# HIVE_BOARD_MCU.net
KiCad netlist of a schematic drawn in Altium Designer
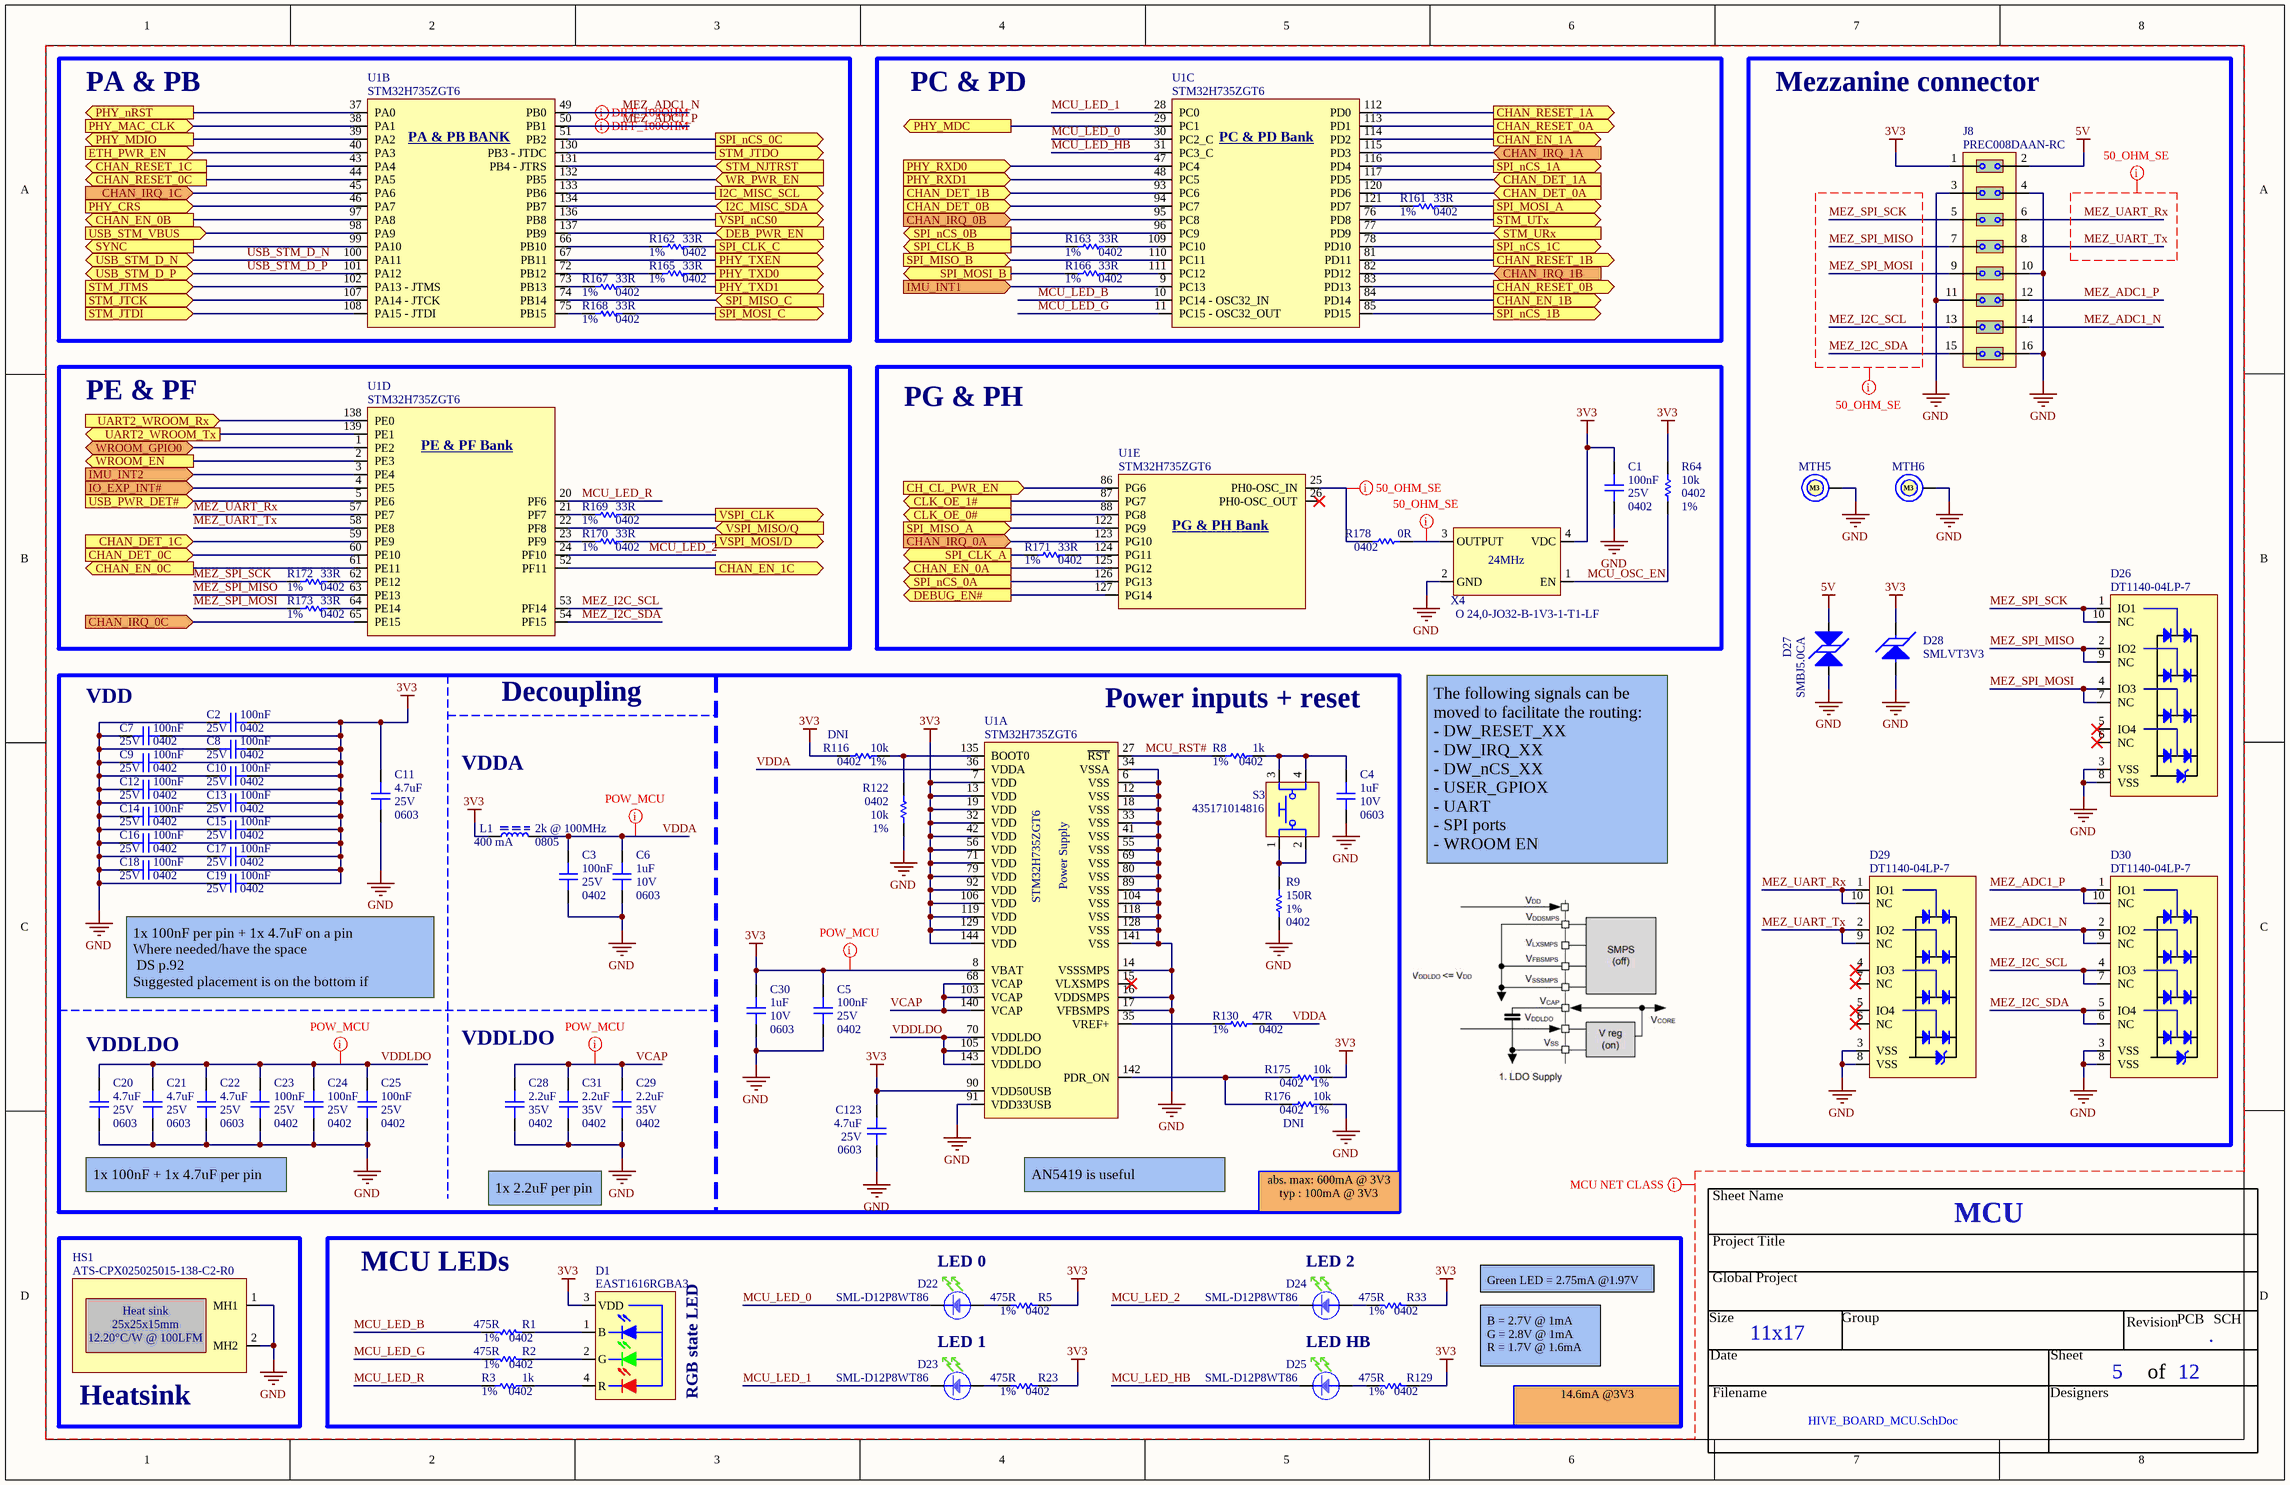
[diagram p0: HIVE_BOARD_MCU.SchDoc]

(export (version "E")
  (design (tool "Eeschema 10.0.6"))
  (components
    (comp (ref "C1")
      (value "100nF")
      (footprint "CAP_CER_0402")
      (description "CAP - CER 0.1µF 10% 25V X7R - 0402")
      (fields
        (field (name "TOLERANCE") "10%")
        (field (name "PACKAGE") "0402")
        (field (name "VOLTAGE RATING") "25V")
        (field (name "Comment") "CGA2B3X7R1E104K050BB")
        (field (name "CREATEDBY/DATE") "Nicolas Roy 2018-11-07")
        (field (name "VERIFIEDBY") "Nicolas V. (2019-01-22)")
      )
      (libsource (lib "GRAMS_MASTER_LIB") (part "CAP_CER_CGA2B3X7R1E104K050BB"))
    )
    (comp (ref "C2")
      (value "100nF")
      (footprint "CAP_CER_0402")
      (description "CAP - CER 0.1µF 10% 25V X7R - 0402")
      (fields
        (field (name "TOLERANCE") "10%")
        (field (name "PACKAGE") "0402")
        (field (name "VOLTAGE RATING") "25V")
        (field (name "Comment") "CGA2B3X7R1E104K050BB")
        (field (name "CREATEDBY/DATE") "Nicolas Roy 2018-11-07")
        (field (name "VERIFIEDBY") "Nicolas V. (2019-01-22)")
      )
      (libsource (lib "GRAMS_MASTER_LIB") (part "CAP_CER_CGA2B3X7R1E104K050BB"))
    )
    (comp (ref "C3")
      (value "100nF")
      (footprint "CAP_CER_0402")
      (description "CAP - CER 0.1µF 10% 25V X7R - 0402")
      (fields
        (field (name "TOLERANCE") "10%")
        (field (name "PACKAGE") "0402")
        (field (name "VOLTAGE RATING") "25V")
        (field (name "Comment") "CGA2B3X7R1E104K050BB")
        (field (name "CREATEDBY/DATE") "Nicolas Roy 2018-11-07")
        (field (name "VERIFIEDBY") "Nicolas V. (2019-01-22)")
      )
      (libsource (lib "GRAMS_MASTER_LIB") (part "CAP_CER_CGA2B3X7R1E104K050BB"))
    )
    (comp (ref "C4")
      (value "1uF")
      (footprint "CAP_CER_0603")
      (description "CAP - CER 1uF 10V 10% X5R - 0603")
      (fields
        (field (name "TOLERANCE") "10%")
        (field (name "PACKAGE") "0603")
        (field (name "VOLTAGE RATING") "10V")
        (field (name "Comment") "C0603C105K8PACTU")
        (field (name "CREATEDBY/DATE") "Hubert Dube - 21/07/20")
        (field (name "VERIFIEDBY") "Louis-Daniel Gaulin - 21/07/20")
      )
      (libsource (lib "SWARMUS_LIB") (part "CAP_CER_C0603C105K8PACTU"))
    )
    (comp (ref "C5")
      (value "100nF")
      (footprint "CAP_CER_0402")
      (description "CAP - CER 0.1µF 10% 25V X7R - 0402")
      (fields
        (field (name "TOLERANCE") "10%")
        (field (name "PACKAGE") "0402")
        (field (name "VOLTAGE RATING") "25V")
        (field (name "Comment") "CGA2B3X7R1E104K050BB")
        (field (name "CREATEDBY/DATE") "Nicolas Roy 2018-11-07")
        (field (name "VERIFIEDBY") "Nicolas V. (2019-01-22)")
      )
      (libsource (lib "GRAMS_MASTER_LIB") (part "CAP_CER_CGA2B3X7R1E104K050BB"))
    )
    (comp (ref "C6")
      (value "1uF")
      (footprint "CAP_CER_0603")
      (description "CAP - CER 1uF 10V 10% X5R - 0603")
      (fields
        (field (name "TOLERANCE") "10%")
        (field (name "PACKAGE") "0603")
        (field (name "VOLTAGE RATING") "10V")
        (field (name "Comment") "C0603C105K8PACTU")
        (field (name "CREATEDBY/DATE") "Hubert Dube - 21/07/20")
        (field (name "VERIFIEDBY") "Louis-Daniel Gaulin - 21/07/20")
      )
      (libsource (lib "SWARMUS_LIB") (part "CAP_CER_C0603C105K8PACTU"))
    )
    (comp (ref "C7")
      (value "100nF")
      (footprint "CAP_CER_0402")
      (description "CAP - CER 0.1µF 10% 25V X7R - 0402")
      (fields
        (field (name "TOLERANCE") "10%")
        (field (name "PACKAGE") "0402")
        (field (name "VOLTAGE RATING") "25V")
        (field (name "Comment") "CGA2B3X7R1E104K050BB")
        (field (name "CREATEDBY/DATE") "Nicolas Roy 2018-11-07")
        (field (name "VERIFIEDBY") "Nicolas V. (2019-01-22)")
      )
      (libsource (lib "GRAMS_MASTER_LIB") (part "CAP_CER_CGA2B3X7R1E104K050BB"))
    )
    (comp (ref "C8")
      (value "100nF")
      (footprint "CAP_CER_0402")
      (description "CAP - CER 0.1µF 10% 25V X7R - 0402")
      (fields
        (field (name "TOLERANCE") "10%")
        (field (name "PACKAGE") "0402")
        (field (name "VOLTAGE RATING") "25V")
        (field (name "Comment") "CGA2B3X7R1E104K050BB")
        (field (name "CREATEDBY/DATE") "Nicolas Roy 2018-11-07")
        (field (name "VERIFIEDBY") "Nicolas V. (2019-01-22)")
      )
      (libsource (lib "GRAMS_MASTER_LIB") (part "CAP_CER_CGA2B3X7R1E104K050BB"))
    )
    (comp (ref "C9")
      (value "100nF")
      (footprint "CAP_CER_0402")
      (description "CAP - CER 0.1µF 10% 25V X7R - 0402")
      (fields
        (field (name "TOLERANCE") "10%")
        (field (name "PACKAGE") "0402")
        (field (name "VOLTAGE RATING") "25V")
        (field (name "Comment") "CGA2B3X7R1E104K050BB")
        (field (name "CREATEDBY/DATE") "Nicolas Roy 2018-11-07")
        (field (name "VERIFIEDBY") "Nicolas V. (2019-01-22)")
      )
      (libsource (lib "GRAMS_MASTER_LIB") (part "CAP_CER_CGA2B3X7R1E104K050BB"))
    )
    (comp (ref "C10")
      (value "100nF")
      (footprint "CAP_CER_0402")
      (description "CAP - CER 0.1µF 10% 25V X7R - 0402")
      (fields
        (field (name "TOLERANCE") "10%")
        (field (name "PACKAGE") "0402")
        (field (name "VOLTAGE RATING") "25V")
        (field (name "Comment") "CGA2B3X7R1E104K050BB")
        (field (name "CREATEDBY/DATE") "Nicolas Roy 2018-11-07")
        (field (name "VERIFIEDBY") "Nicolas V. (2019-01-22)")
      )
      (libsource (lib "GRAMS_MASTER_LIB") (part "CAP_CER_CGA2B3X7R1E104K050BB"))
    )
    (comp (ref "C11")
      (value "4.7uF")
      (footprint "CAP_CER_0603")
      (description "CAP - CER 4.7µF 20% 25V X5R - 0603")
      (fields
        (field (name "TOLERANCE") "20%")
        (field (name "PACKAGE") "0603")
        (field (name "VOLTAGE RATING") "25V")
        (field (name "Comment") "CL10A475MA8NQNC")
        (field (name "CREATEDBY/DATE") "Nicolas Roy 2018-11-21")
        (field (name "VERIFIEDBY") "Nicolas V. (2019-01-22)")
      )
      (libsource (lib "GRAMS_MASTER_LIB") (part "CAP_CER_CL10A475MA8NQNC"))
    )
    (comp (ref "C12")
      (value "100nF")
      (footprint "CAP_CER_0402")
      (description "CAP - CER 0.1µF 10% 25V X7R - 0402")
      (fields
        (field (name "TOLERANCE") "10%")
        (field (name "PACKAGE") "0402")
        (field (name "VOLTAGE RATING") "25V")
        (field (name "Comment") "CGA2B3X7R1E104K050BB")
        (field (name "CREATEDBY/DATE") "Nicolas Roy 2018-11-07")
        (field (name "VERIFIEDBY") "Nicolas V. (2019-01-22)")
      )
      (libsource (lib "GRAMS_MASTER_LIB") (part "CAP_CER_CGA2B3X7R1E104K050BB"))
    )
    (comp (ref "C13")
      (value "100nF")
      (footprint "CAP_CER_0402")
      (description "CAP - CER 0.1µF 10% 25V X7R - 0402")
      (fields
        (field (name "TOLERANCE") "10%")
        (field (name "PACKAGE") "0402")
        (field (name "VOLTAGE RATING") "25V")
        (field (name "Comment") "CGA2B3X7R1E104K050BB")
        (field (name "CREATEDBY/DATE") "Nicolas Roy 2018-11-07")
        (field (name "VERIFIEDBY") "Nicolas V. (2019-01-22)")
      )
      (libsource (lib "GRAMS_MASTER_LIB") (part "CAP_CER_CGA2B3X7R1E104K050BB"))
    )
    (comp (ref "C14")
      (value "100nF")
      (footprint "CAP_CER_0402")
      (description "CAP - CER 0.1µF 10% 25V X7R - 0402")
      (fields
        (field (name "TOLERANCE") "10%")
        (field (name "PACKAGE") "0402")
        (field (name "VOLTAGE RATING") "25V")
        (field (name "Comment") "CGA2B3X7R1E104K050BB")
        (field (name "CREATEDBY/DATE") "Nicolas Roy 2018-11-07")
        (field (name "VERIFIEDBY") "Nicolas V. (2019-01-22)")
      )
      (libsource (lib "GRAMS_MASTER_LIB") (part "CAP_CER_CGA2B3X7R1E104K050BB"))
    )
    (comp (ref "C15")
      (value "100nF")
      (footprint "CAP_CER_0402")
      (description "CAP - CER 0.1µF 10% 25V X7R - 0402")
      (fields
        (field (name "TOLERANCE") "10%")
        (field (name "PACKAGE") "0402")
        (field (name "VOLTAGE RATING") "25V")
        (field (name "Comment") "CGA2B3X7R1E104K050BB")
        (field (name "CREATEDBY/DATE") "Nicolas Roy 2018-11-07")
        (field (name "VERIFIEDBY") "Nicolas V. (2019-01-22)")
      )
      (libsource (lib "GRAMS_MASTER_LIB") (part "CAP_CER_CGA2B3X7R1E104K050BB"))
    )
    (comp (ref "C16")
      (value "100nF")
      (footprint "CAP_CER_0402")
      (description "CAP - CER 0.1µF 10% 25V X7R - 0402")
      (fields
        (field (name "TOLERANCE") "10%")
        (field (name "PACKAGE") "0402")
        (field (name "VOLTAGE RATING") "25V")
        (field (name "Comment") "CGA2B3X7R1E104K050BB")
        (field (name "CREATEDBY/DATE") "Nicolas Roy 2018-11-07")
        (field (name "VERIFIEDBY") "Nicolas V. (2019-01-22)")
      )
      (libsource (lib "GRAMS_MASTER_LIB") (part "CAP_CER_CGA2B3X7R1E104K050BB"))
    )
    (comp (ref "C17")
      (value "100nF")
      (footprint "CAP_CER_0402")
      (description "CAP - CER 0.1µF 10% 25V X7R - 0402")
      (fields
        (field (name "TOLERANCE") "10%")
        (field (name "PACKAGE") "0402")
        (field (name "VOLTAGE RATING") "25V")
        (field (name "Comment") "CGA2B3X7R1E104K050BB")
        (field (name "CREATEDBY/DATE") "Nicolas Roy 2018-11-07")
        (field (name "VERIFIEDBY") "Nicolas V. (2019-01-22)")
      )
      (libsource (lib "GRAMS_MASTER_LIB") (part "CAP_CER_CGA2B3X7R1E104K050BB"))
    )
    (comp (ref "C18")
      (value "100nF")
      (footprint "CAP_CER_0402")
      (description "CAP - CER 0.1µF 10% 25V X7R - 0402")
      (fields
        (field (name "TOLERANCE") "10%")
        (field (name "PACKAGE") "0402")
        (field (name "VOLTAGE RATING") "25V")
        (field (name "Comment") "CGA2B3X7R1E104K050BB")
        (field (name "CREATEDBY/DATE") "Nicolas Roy 2018-11-07")
        (field (name "VERIFIEDBY") "Nicolas V. (2019-01-22)")
      )
      (libsource (lib "GRAMS_MASTER_LIB") (part "CAP_CER_CGA2B3X7R1E104K050BB"))
    )
    (comp (ref "C19")
      (value "100nF")
      (footprint "CAP_CER_0402")
      (description "CAP - CER 0.1µF 10% 25V X7R - 0402")
      (fields
        (field (name "TOLERANCE") "10%")
        (field (name "PACKAGE") "0402")
        (field (name "VOLTAGE RATING") "25V")
        (field (name "Comment") "CGA2B3X7R1E104K050BB")
        (field (name "CREATEDBY/DATE") "Nicolas Roy 2018-11-07")
        (field (name "VERIFIEDBY") "Nicolas V. (2019-01-22)")
      )
      (libsource (lib "GRAMS_MASTER_LIB") (part "CAP_CER_CGA2B3X7R1E104K050BB"))
    )
    (comp (ref "C20")
      (value "4.7uF")
      (footprint "CAP_CER_0603")
      (description "CAP - CER 4.7µF 20% 25V X5R - 0603")
      (fields
        (field (name "TOLERANCE") "20%")
        (field (name "PACKAGE") "0603")
        (field (name "VOLTAGE RATING") "25V")
        (field (name "Comment") "CL10A475MA8NQNC")
        (field (name "CREATEDBY/DATE") "Nicolas Roy 2018-11-21")
        (field (name "VERIFIEDBY") "Nicolas V. (2019-01-22)")
      )
      (libsource (lib "GRAMS_MASTER_LIB") (part "CAP_CER_CL10A475MA8NQNC"))
    )
    (comp (ref "C21")
      (value "4.7uF")
      (footprint "CAP_CER_0603")
      (description "CAP - CER 4.7µF 20% 25V X5R - 0603")
      (fields
        (field (name "TOLERANCE") "20%")
        (field (name "PACKAGE") "0603")
        (field (name "VOLTAGE RATING") "25V")
        (field (name "Comment") "CL10A475MA8NQNC")
        (field (name "CREATEDBY/DATE") "Nicolas Roy 2018-11-21")
        (field (name "VERIFIEDBY") "Nicolas V. (2019-01-22)")
      )
      (libsource (lib "GRAMS_MASTER_LIB") (part "CAP_CER_CL10A475MA8NQNC"))
    )
    (comp (ref "C22")
      (value "4.7uF")
      (footprint "CAP_CER_0603")
      (description "CAP - CER 4.7µF 20% 25V X5R - 0603")
      (fields
        (field (name "TOLERANCE") "20%")
        (field (name "PACKAGE") "0603")
        (field (name "VOLTAGE RATING") "25V")
        (field (name "Comment") "CL10A475MA8NQNC")
        (field (name "CREATEDBY/DATE") "Nicolas Roy 2018-11-21")
        (field (name "VERIFIEDBY") "Nicolas V. (2019-01-22)")
      )
      (libsource (lib "GRAMS_MASTER_LIB") (part "CAP_CER_CL10A475MA8NQNC"))
    )
    (comp (ref "C23")
      (value "100nF")
      (footprint "CAP_CER_0402")
      (description "CAP - CER 0.1µF 10% 25V X7R - 0402")
      (fields
        (field (name "TOLERANCE") "10%")
        (field (name "PACKAGE") "0402")
        (field (name "VOLTAGE RATING") "25V")
        (field (name "Comment") "CGA2B3X7R1E104K050BB")
        (field (name "CREATEDBY/DATE") "Nicolas Roy 2018-11-07")
        (field (name "VERIFIEDBY") "Nicolas V. (2019-01-22)")
      )
      (libsource (lib "GRAMS_MASTER_LIB") (part "CAP_CER_CGA2B3X7R1E104K050BB"))
    )
    (comp (ref "C24")
      (value "100nF")
      (footprint "CAP_CER_0402")
      (description "CAP - CER 0.1µF 10% 25V X7R - 0402")
      (fields
        (field (name "TOLERANCE") "10%")
        (field (name "PACKAGE") "0402")
        (field (name "VOLTAGE RATING") "25V")
        (field (name "Comment") "CGA2B3X7R1E104K050BB")
        (field (name "CREATEDBY/DATE") "Nicolas Roy 2018-11-07")
        (field (name "VERIFIEDBY") "Nicolas V. (2019-01-22)")
      )
      (libsource (lib "GRAMS_MASTER_LIB") (part "CAP_CER_CGA2B3X7R1E104K050BB"))
    )
    (comp (ref "C25")
      (value "100nF")
      (footprint "CAP_CER_0402")
      (description "CAP - CER 0.1µF 10% 25V X7R - 0402")
      (fields
        (field (name "TOLERANCE") "10%")
        (field (name "PACKAGE") "0402")
        (field (name "VOLTAGE RATING") "25V")
        (field (name "Comment") "CGA2B3X7R1E104K050BB")
        (field (name "CREATEDBY/DATE") "Nicolas Roy 2018-11-07")
        (field (name "VERIFIEDBY") "Nicolas V. (2019-01-22)")
      )
      (libsource (lib "GRAMS_MASTER_LIB") (part "CAP_CER_CGA2B3X7R1E104K050BB"))
    )
    (comp (ref "C28")
      (value "2.2uF")
      (footprint "CAP_CER_0402")
      (description "CAP - CER 2.2µF 10% 35V X5R - 0402")
      (fields
        (field (name "TOLERANCE") "10%")
        (field (name "PACKAGE") "0402")
        (field (name "VOLTAGE RATING") "35V")
        (field (name "Comment") "C1005X5R1V225K050BC")
        (field (name "CREATEDBY/DATE") "Nicolas Roy 2018-10-17")
        (field (name "VERIFIEDBY") "Caroline Paulin - 18 janv 2018")
      )
      (libsource (lib "GRAMS_MASTER_LIB") (part "CAP_CER_C1005X5R1V225K050BC"))
    )
    (comp (ref "C29")
      (value "2.2uF")
      (footprint "CAP_CER_0402")
      (description "CAP - CER 2.2µF 10% 35V X5R - 0402")
      (fields
        (field (name "TOLERANCE") "10%")
        (field (name "PACKAGE") "0402")
        (field (name "VOLTAGE RATING") "35V")
        (field (name "Comment") "C1005X5R1V225K050BC")
        (field (name "CREATEDBY/DATE") "Nicolas Roy 2018-10-17")
        (field (name "VERIFIEDBY") "Caroline Paulin - 18 janv 2018")
      )
      (libsource (lib "GRAMS_MASTER_LIB") (part "CAP_CER_C1005X5R1V225K050BC"))
    )
    (comp (ref "C30")
      (value "1uF")
      (footprint "CAP_CER_0603")
      (description "CAP - CER 1uF 10V 10% X5R - 0603")
      (fields
        (field (name "TOLERANCE") "10%")
        (field (name "PACKAGE") "0603")
        (field (name "VOLTAGE RATING") "10V")
        (field (name "Comment") "C0603C105K8PACTU")
        (field (name "CREATEDBY/DATE") "Hubert Dube - 21/07/20")
        (field (name "VERIFIEDBY") "Louis-Daniel Gaulin - 21/07/20")
      )
      (libsource (lib "SWARMUS_LIB") (part "CAP_CER_C0603C105K8PACTU"))
    )
    (comp (ref "C31")
      (value "2.2uF")
      (footprint "CAP_CER_0402")
      (description "CAP - CER 2.2µF 10% 35V X5R - 0402")
      (fields
        (field (name "TOLERANCE") "10%")
        (field (name "PACKAGE") "0402")
        (field (name "VOLTAGE RATING") "35V")
        (field (name "Comment") "C1005X5R1V225K050BC")
        (field (name "CREATEDBY/DATE") "Nicolas Roy 2018-10-17")
        (field (name "VERIFIEDBY") "Caroline Paulin - 18 janv 2018")
      )
      (libsource (lib "GRAMS_MASTER_LIB") (part "CAP_CER_C1005X5R1V225K050BC"))
    )
    (comp (ref "C123")
      (value "4.7uF")
      (footprint "CAP_CER_0603")
      (description "CAP - CER 4.7µF 20% 25V X5R - 0603")
      (fields
        (field (name "TOLERANCE") "20%")
        (field (name "PACKAGE") "0603")
        (field (name "VOLTAGE RATING") "25V")
        (field (name "Comment") "CL10A475MA8NQNC")
        (field (name "CREATEDBY/DATE") "Nicolas Roy 2018-11-21")
        (field (name "VERIFIEDBY") "Nicolas V. (2019-01-22)")
      )
      (libsource (lib "GRAMS_MASTER_LIB") (part "CAP_CER_CL10A475MA8NQNC"))
    )
    (comp (ref "D1")
      (value "EAST1616RGBA3")
      (footprint "DIO_EAST1616RGBA3")
      (fields
        (field (name "TOLERANCE") "±50ppm")
        (field (name "CREATEDBY/DATE") "Hubert Dube - 26/02/2021")
        (field (name "VERIFIEDBY") "PA + Hubert Dube - 19/03/2021")
      )
      (libsource (lib "SWARMUS_LIB") (part "DIO_EAST1616RGBA3"))
    )
    (comp (ref "D22")
      (value "SML-D12P8WT86")
      (footprint "LED_SML-D12P8WT86")
      (description "LED - GREEN DIFFUSED 0603 SMD - 0603")
      (fields
        (field (name "CREATEDBY/DATE") "Keven Deslandes - 2018/11/21")
        (field (name "VERIFIEDBY") "Caroline Paulin - 13 février 2019")
      )
      (libsource (lib "GRAMS_MASTER_LIB") (part "LED_SML-D12P8WT86"))
    )
    (comp (ref "D23")
      (value "SML-D12P8WT86")
      (footprint "LED_SML-D12P8WT86")
      (description "LED - GREEN DIFFUSED 0603 SMD - 0603")
      (fields
        (field (name "CREATEDBY/DATE") "Keven Deslandes - 2018/11/21")
        (field (name "VERIFIEDBY") "Caroline Paulin - 13 février 2019")
      )
      (libsource (lib "GRAMS_MASTER_LIB") (part "LED_SML-D12P8WT86"))
    )
    (comp (ref "D24")
      (value "SML-D12P8WT86")
      (footprint "LED_SML-D12P8WT86")
      (description "LED - GREEN DIFFUSED 0603 SMD - 0603")
      (fields
        (field (name "CREATEDBY/DATE") "Keven Deslandes - 2018/11/21")
        (field (name "VERIFIEDBY") "Caroline Paulin - 13 février 2019")
      )
      (libsource (lib "GRAMS_MASTER_LIB") (part "LED_SML-D12P8WT86"))
    )
    (comp (ref "D25")
      (value "SML-D12P8WT86")
      (footprint "LED_SML-D12P8WT86")
      (description "LED - GREEN DIFFUSED 0603 SMD - 0603")
      (fields
        (field (name "CREATEDBY/DATE") "Keven Deslandes - 2018/11/21")
        (field (name "VERIFIEDBY") "Caroline Paulin - 13 février 2019")
      )
      (libsource (lib "GRAMS_MASTER_LIB") (part "LED_SML-D12P8WT86"))
    )
    (comp (ref "D26")
      (value "DT1140-04LP-7")
      (footprint "TVS_DATA_DT1140-04LP-7")
      (description "TVS - DIODE 5.5V 10V - 10-UFDFN")
      (fields
        (field (name "CREATEDBY/DATE") "Joël Lemay 2019-11-20")
        (field (name "VERIFIEDBY") "C.Paulin - 21/11/2019")
      )
      (libsource (lib "GRAMS_MASTER_LIB") (part "TVS_DATA_DT1140-04LP-7"))
    )
    (comp (ref "D27")
      (value "SMBJ5.0CA")
      (footprint "TVS_PWR_SMBJ5.0CA")
      (description "TVS - BIDIR 5V 9.2V 600W - DO214AA")
      (fields
        (field (name "CREATEDBY/DATE") "Jonathan Bouchard - 2019-03-22")
        (field (name "VERIFIEDBY") "Nicolas V. (2019-05-06)")
      )
      (libsource (lib "GRAMS_MASTER_LIB") (part "TVS_PWR_SMBJ5.0CA"))
    )
    (comp (ref "D28")
      (value "SMLVT3V3")
      (footprint "TVS_POW_SMLVT3V3")
      (description "TVS - 3.3V 10.3V 600W - DO214AA")
      (fields
        (field (name "CREATEDBY/DATE") "Jonathan Bouchard - 2019-04-27")
        (field (name "VERIFIEDBY") "Nicolas V. (2019-05-06)")
      )
      (libsource (lib "GRAMS_MASTER_LIB") (part "TVS_POW_SMLVT3V3"))
    )
    (comp (ref "D29")
      (value "DT1140-04LP-7")
      (footprint "TVS_DATA_DT1140-04LP-7")
      (description "TVS - DIODE 5.5V 10V - 10-UFDFN")
      (fields
        (field (name "CREATEDBY/DATE") "Joël Lemay 2019-11-20")
        (field (name "VERIFIEDBY") "C.Paulin - 21/11/2019")
      )
      (libsource (lib "GRAMS_MASTER_LIB") (part "TVS_DATA_DT1140-04LP-7"))
    )
    (comp (ref "D30")
      (value "DT1140-04LP-7")
      (footprint "TVS_DATA_DT1140-04LP-7")
      (description "TVS - DIODE 5.5V 10V - 10-UFDFN")
      (fields
        (field (name "CREATEDBY/DATE") "Joël Lemay 2019-11-20")
        (field (name "VERIFIEDBY") "C.Paulin - 21/11/2019")
      )
      (libsource (lib "GRAMS_MASTER_LIB") (part "TVS_DATA_DT1140-04LP-7"))
    )
    (comp (ref "HS1")
      (value "ATS-CPX025025015-138-C2-R0")
      (footprint "THE_HS_ATS-CPX025025015-138-C2-R0")
      (description "THE_HS - Heat Sink  25x25x15 mm - TH M3")
      (fields
        (field (name "CREATEDBY/DATE") "Philippe Arsenault/2021-04-08")
        (field (name "VERIFIEDBY") "Louis-Daniel Gaulin / 14-04-2021")
      )
      (libsource (lib "SWARMUS_LIB") (part "THE_HS_ATS-CPX025025015-138-C2-R0"))
    )
    (comp (ref "J8")
      (value "PREC008DAAN-RC")
      (footprint "CON_HDR_PREC008DAAN-RC")
      (description "CON - Connector Header Through Hole 16 position 0.100\" (2.54mm)")
      (fields
        (field (name "VERIFIEDBY") "Philippe Arsenault/2021-03-25")
        (field (name "CREATEDBY/DATE") "Hubert Dube -  16/03/2021")
      )
      (libsource (lib "SWARMUS_LIB") (part "CON_HDR_PREC008DAAN-RC"))
    )
    (comp (ref "L1")
      (value "2k @ 100MHz")
      (footprint "FER_0805")
      (description "FER - FERRITE BEAD 2 KOHM @ 100 MHz 400 mA - 0805")
      (fields
        (field (name "CURRENT RATING") "400 mA")
        (field (name "PACKAGE") "0805")
        (field (name "Comment") "MMZ2012Y202BT000")
        (field (name "CREATEDBY/DATE") "Hubert Dube - 7/02/2021")
        (field (name "VERIFIEDBY") "Philippe Arsenault/ 2021-03-13")
      )
      (libsource (lib "SWARMUS_LIB") (part "FER_MMZ2012Y202BT000"))
    )
    (comp (ref "MTH5")
      (value "M3")
      (footprint "MTH_M3")
      (description "MTH - MOUNTING HOLE M3 PLATED - M3")
      (fields
        (field (name "CREATEDBY/DATE") "Jonathan Bouchard 2018-07-23")
        (field (name "VERIFIEDBY") "Arnaud Samson 23-07-18")
      )
      (libsource (lib "GRAMS_MASTER_LIB") (part "MTH_M3"))
    )
    (comp (ref "MTH6")
      (value "M3")
      (footprint "MTH_M3")
      (description "MTH - MOUNTING HOLE M3 PLATED - M3")
      (fields
        (field (name "CREATEDBY/DATE") "Jonathan Bouchard 2018-07-23")
        (field (name "VERIFIEDBY") "Arnaud Samson 23-07-18")
      )
      (libsource (lib "GRAMS_MASTER_LIB") (part "MTH_M3"))
    )
    (comp (ref "R1")
      (value "475R")
      (footprint "RES_0402")
      (description "RES - 475R 1% 1/10W- 0402")
      (fields
        (field (name "TOLERANCE") "1%")
        (field (name "PACKAGE") "0402")
        (field (name "Comment") "ERJ-2RKF4750X")
        (field (name "CREATEDBY/DATE") "Keven Deslandes 2018-10-17")
        (field (name "VERIFIEDBY") "Carolilne Paulin - 18/12/2018")
      )
      (libsource (lib "GRAMS_MASTER_LIB") (part "RES_ERJ-2RKF4750X"))
    )
    (comp (ref "R2")
      (value "475R")
      (footprint "RES_0402")
      (description "RES - 475R 1% 1/10W- 0402")
      (fields
        (field (name "TOLERANCE") "1%")
        (field (name "PACKAGE") "0402")
        (field (name "Comment") "ERJ-2RKF4750X")
        (field (name "CREATEDBY/DATE") "Keven Deslandes 2018-10-17")
        (field (name "VERIFIEDBY") "Carolilne Paulin - 18/12/2018")
      )
      (libsource (lib "GRAMS_MASTER_LIB") (part "RES_ERJ-2RKF4750X"))
    )
    (comp (ref "R3")
      (value "1k")
      (footprint "RES_0402")
      (description "RES - 1K OHM 1% 1/16W - 0402")
      (fields
        (field (name "TOLERANCE") "1%")
        (field (name "PACKAGE") "0402")
        (field (name "Comment") "RC0402FR-071KL")
        (field (name "CREATEDBY/DATE") "Jonathan Bouchard 2018-07-05")
        (field (name "VERIFIEDBY") "Arnaud Samson 16-07-18")
      )
      (libsource (lib "GRAMS_MASTER_LIB") (part "RES_RC0402FR-071KL"))
    )
    (comp (ref "R5")
      (value "475R")
      (footprint "RES_0402")
      (description "RES - 475R 1% 1/10W- 0402")
      (fields
        (field (name "TOLERANCE") "1%")
        (field (name "PACKAGE") "0402")
        (field (name "Comment") "ERJ-2RKF4750X")
        (field (name "CREATEDBY/DATE") "Keven Deslandes 2018-10-17")
        (field (name "VERIFIEDBY") "Carolilne Paulin - 18/12/2018")
      )
      (libsource (lib "GRAMS_MASTER_LIB") (part "RES_ERJ-2RKF4750X"))
    )
    (comp (ref "R8")
      (value "1k")
      (footprint "RES_0402")
      (description "RES - 1K OHM 1% 1/16W - 0402")
      (fields
        (field (name "TOLERANCE") "1%")
        (field (name "PACKAGE") "0402")
        (field (name "Comment") "RC0402FR-071KL")
        (field (name "CREATEDBY/DATE") "Jonathan Bouchard 2018-07-05")
        (field (name "VERIFIEDBY") "Arnaud Samson 16-07-18")
      )
      (libsource (lib "GRAMS_MASTER_LIB") (part "RES_RC0402FR-071KL"))
    )
    (comp (ref "R9")
      (value "150R")
      (footprint "RES_0402")
      (description "RES - 150R 1% 1/16W - 0402")
      (fields
        (field (name "TOLERANCE") "1%")
        (field (name "PACKAGE") "0402")
        (field (name "Comment") "RC0402FR-07150RL")
        (field (name "CREATEDBY/DATE") "Jonathan Bouchard 2019-03-25")
        (field (name "VERIFIEDBY") "Nicolas V. (2019-05-02)")
      )
      (libsource (lib "GRAMS_MASTER_LIB") (part "RES_RC0402FR-07150RL"))
    )
    (comp (ref "R23")
      (value "475R")
      (footprint "RES_0402")
      (description "RES - 475R 1% 1/10W- 0402")
      (fields
        (field (name "TOLERANCE") "1%")
        (field (name "PACKAGE") "0402")
        (field (name "Comment") "ERJ-2RKF4750X")
        (field (name "CREATEDBY/DATE") "Keven Deslandes 2018-10-17")
        (field (name "VERIFIEDBY") "Carolilne Paulin - 18/12/2018")
      )
      (libsource (lib "GRAMS_MASTER_LIB") (part "RES_ERJ-2RKF4750X"))
    )
    (comp (ref "R33")
      (value "475R")
      (footprint "RES_0402")
      (description "RES - 475R 1% 1/10W- 0402")
      (fields
        (field (name "TOLERANCE") "1%")
        (field (name "PACKAGE") "0402")
        (field (name "Comment") "ERJ-2RKF4750X")
        (field (name "CREATEDBY/DATE") "Keven Deslandes 2018-10-17")
        (field (name "VERIFIEDBY") "Carolilne Paulin - 18/12/2018")
      )
      (libsource (lib "GRAMS_MASTER_LIB") (part "RES_ERJ-2RKF4750X"))
    )
    (comp (ref "R64")
      (value "10k")
      (footprint "RES_0402")
      (description "RES - 10K OHMS 1% 1/16W - 0402")
      (fields
        (field (name "TOLERANCE") "1%")
        (field (name "PACKAGE") "0402")
        (field (name "Comment") "RC0402FR-0710KL")
        (field (name "CREATEDBY/DATE") "Nicolas V. (2018-11-20)")
        (field (name "VERIFIEDBY") "Nicolas V. (2018-11-20)")
      )
      (libsource (lib "GRAMS_MASTER_LIB") (part "RES_RC0402FR-0710KL"))
    )
    (comp (ref "R116")
      (value "10k")
      (footprint "RES_0402")
      (description "RES - 10K OHMS 1% 1/16W - 0402")
      (fields
        (field (name "TOLERANCE") "1%")
        (field (name "ASSEMBLY NOTE") "DNI")
        (field (name "PACKAGE") "0402")
        (field (name "Comment") "RC0402FR-0710KL")
        (field (name "CREATEDBY/DATE") "Nicolas V. (2018-11-20)")
        (field (name "VERIFIEDBY") "Nicolas V. (2018-11-20)")
      )
      (libsource (lib "GRAMS_MASTER_LIB") (part "RES_RC0402FR-0710KL"))
    )
    (comp (ref "R122")
      (value "10k")
      (footprint "RES_0402")
      (description "RES - 10K OHMS 1% 1/16W - 0402")
      (fields
        (field (name "TOLERANCE") "1%")
        (field (name "PACKAGE") "0402")
        (field (name "Comment") "RC0402FR-0710KL")
        (field (name "CREATEDBY/DATE") "Nicolas V. (2018-11-20)")
        (field (name "VERIFIEDBY") "Nicolas V. (2018-11-20)")
      )
      (libsource (lib "GRAMS_MASTER_LIB") (part "RES_RC0402FR-0710KL"))
    )
    (comp (ref "R129")
      (value "475R")
      (footprint "RES_0402")
      (description "RES - 475R 1% 1/10W- 0402")
      (fields
        (field (name "TOLERANCE") "1%")
        (field (name "PACKAGE") "0402")
        (field (name "Comment") "ERJ-2RKF4750X")
        (field (name "CREATEDBY/DATE") "Keven Deslandes 2018-10-17")
        (field (name "VERIFIEDBY") "Carolilne Paulin - 18/12/2018")
      )
      (libsource (lib "GRAMS_MASTER_LIB") (part "RES_ERJ-2RKF4750X"))
    )
    (comp (ref "R130")
      (value "47R")
      (footprint "RES_0402")
      (description "RES -  47ohm ±1% 0.063W, 1/16W Chip Resistor 0402")
      (fields
        (field (name "TOLERANCE") "1%")
        (field (name "PACKAGE") "0402")
        (field (name "Comment") "RC0402FR-0747RL")
        (field (name "CREATEDBY/DATE") "Philippe Arsenault/2021-04-10")
        (field (name "VERIFIEDBY") "Louis-Daniel Gaulin / 14-04-2021")
      )
      (libsource (lib "SWARMUS_LIB") (part "RES_RC0402FR-0747RL"))
    )
    (comp (ref "R161")
      (value "33R")
      (footprint "RES_0402")
      (description "RES - 33 OHM 1% 1/16W - 0402")
      (fields
        (field (name "TOLERANCE") "1%")
        (field (name "PACKAGE") "0402")
        (field (name "Comment") "RC0402FR-0733RL")
        (field (name "CREATEDBY/DATE") "Louis-Daniel Gaulin/ 14/01/2020")
        (field (name "VERIFIEDBY") "C.Paulin - 21/01/2020")
      )
      (libsource (lib "GRAMS_MASTER_LIB") (part "RES_RC0402FR-0733RL"))
    )
    (comp (ref "R162")
      (value "33R")
      (footprint "RES_0402")
      (description "RES - 33 OHM 1% 1/16W - 0402")
      (fields
        (field (name "TOLERANCE") "1%")
        (field (name "PACKAGE") "0402")
        (field (name "Comment") "RC0402FR-0733RL")
        (field (name "CREATEDBY/DATE") "Louis-Daniel Gaulin/ 14/01/2020")
        (field (name "VERIFIEDBY") "C.Paulin - 21/01/2020")
      )
      (libsource (lib "GRAMS_MASTER_LIB") (part "RES_RC0402FR-0733RL"))
    )
    (comp (ref "R163")
      (value "33R")
      (footprint "RES_0402")
      (description "RES - 33 OHM 1% 1/16W - 0402")
      (fields
        (field (name "TOLERANCE") "1%")
        (field (name "PACKAGE") "0402")
        (field (name "Comment") "RC0402FR-0733RL")
        (field (name "CREATEDBY/DATE") "Louis-Daniel Gaulin/ 14/01/2020")
        (field (name "VERIFIEDBY") "C.Paulin - 21/01/2020")
      )
      (libsource (lib "GRAMS_MASTER_LIB") (part "RES_RC0402FR-0733RL"))
    )
    (comp (ref "R165")
      (value "33R")
      (footprint "RES_0402")
      (description "RES - 33 OHM 1% 1/16W - 0402")
      (fields
        (field (name "TOLERANCE") "1%")
        (field (name "PACKAGE") "0402")
        (field (name "Comment") "RC0402FR-0733RL")
        (field (name "CREATEDBY/DATE") "Louis-Daniel Gaulin/ 14/01/2020")
        (field (name "VERIFIEDBY") "C.Paulin - 21/01/2020")
      )
      (libsource (lib "GRAMS_MASTER_LIB") (part "RES_RC0402FR-0733RL"))
    )
    (comp (ref "R166")
      (value "33R")
      (footprint "RES_0402")
      (description "RES - 33 OHM 1% 1/16W - 0402")
      (fields
        (field (name "TOLERANCE") "1%")
        (field (name "PACKAGE") "0402")
        (field (name "Comment") "RC0402FR-0733RL")
        (field (name "CREATEDBY/DATE") "Louis-Daniel Gaulin/ 14/01/2020")
        (field (name "VERIFIEDBY") "C.Paulin - 21/01/2020")
      )
      (libsource (lib "GRAMS_MASTER_LIB") (part "RES_RC0402FR-0733RL"))
    )
    (comp (ref "R167")
      (value "33R")
      (footprint "RES_0402")
      (description "RES - 33 OHM 1% 1/16W - 0402")
      (fields
        (field (name "TOLERANCE") "1%")
        (field (name "PACKAGE") "0402")
        (field (name "Comment") "RC0402FR-0733RL")
        (field (name "CREATEDBY/DATE") "Louis-Daniel Gaulin/ 14/01/2020")
        (field (name "VERIFIEDBY") "C.Paulin - 21/01/2020")
      )
      (libsource (lib "GRAMS_MASTER_LIB") (part "RES_RC0402FR-0733RL"))
    )
    (comp (ref "R168")
      (value "33R")
      (footprint "RES_0402")
      (description "RES - 33 OHM 1% 1/16W - 0402")
      (fields
        (field (name "TOLERANCE") "1%")
        (field (name "PACKAGE") "0402")
        (field (name "Comment") "RC0402FR-0733RL")
        (field (name "CREATEDBY/DATE") "Louis-Daniel Gaulin/ 14/01/2020")
        (field (name "VERIFIEDBY") "C.Paulin - 21/01/2020")
      )
      (libsource (lib "GRAMS_MASTER_LIB") (part "RES_RC0402FR-0733RL"))
    )
    (comp (ref "R169")
      (value "33R")
      (footprint "RES_0402")
      (description "RES - 33 OHM 1% 1/16W - 0402")
      (fields
        (field (name "TOLERANCE") "1%")
        (field (name "PACKAGE") "0402")
        (field (name "Comment") "RC0402FR-0733RL")
        (field (name "CREATEDBY/DATE") "Louis-Daniel Gaulin/ 14/01/2020")
        (field (name "VERIFIEDBY") "C.Paulin - 21/01/2020")
      )
      (libsource (lib "GRAMS_MASTER_LIB") (part "RES_RC0402FR-0733RL"))
    )
    (comp (ref "R170")
      (value "33R")
      (footprint "RES_0402")
      (description "RES - 33 OHM 1% 1/16W - 0402")
      (fields
        (field (name "TOLERANCE") "1%")
        (field (name "PACKAGE") "0402")
        (field (name "Comment") "RC0402FR-0733RL")
        (field (name "CREATEDBY/DATE") "Louis-Daniel Gaulin/ 14/01/2020")
        (field (name "VERIFIEDBY") "C.Paulin - 21/01/2020")
      )
      (libsource (lib "GRAMS_MASTER_LIB") (part "RES_RC0402FR-0733RL"))
    )
    (comp (ref "R171")
      (value "33R")
      (footprint "RES_0402")
      (description "RES - 33 OHM 1% 1/16W - 0402")
      (fields
        (field (name "TOLERANCE") "1%")
        (field (name "PACKAGE") "0402")
        (field (name "Comment") "RC0402FR-0733RL")
        (field (name "CREATEDBY/DATE") "Louis-Daniel Gaulin/ 14/01/2020")
        (field (name "VERIFIEDBY") "C.Paulin - 21/01/2020")
      )
      (libsource (lib "GRAMS_MASTER_LIB") (part "RES_RC0402FR-0733RL"))
    )
    (comp (ref "R172")
      (value "33R")
      (footprint "RES_0402")
      (description "RES - 33 OHM 1% 1/16W - 0402")
      (fields
        (field (name "TOLERANCE") "1%")
        (field (name "PACKAGE") "0402")
        (field (name "Comment") "RC0402FR-0733RL")
        (field (name "CREATEDBY/DATE") "Louis-Daniel Gaulin/ 14/01/2020")
        (field (name "VERIFIEDBY") "C.Paulin - 21/01/2020")
      )
      (libsource (lib "GRAMS_MASTER_LIB") (part "RES_RC0402FR-0733RL"))
    )
    (comp (ref "R173")
      (value "33R")
      (footprint "RES_0402")
      (description "RES - 33 OHM 1% 1/16W - 0402")
      (fields
        (field (name "TOLERANCE") "1%")
        (field (name "PACKAGE") "0402")
        (field (name "Comment") "RC0402FR-0733RL")
        (field (name "CREATEDBY/DATE") "Louis-Daniel Gaulin/ 14/01/2020")
        (field (name "VERIFIEDBY") "C.Paulin - 21/01/2020")
      )
      (libsource (lib "GRAMS_MASTER_LIB") (part "RES_RC0402FR-0733RL"))
    )
    (comp (ref "R175")
      (value "10k")
      (footprint "RES_0402")
      (description "RES - 10K OHMS 1% 1/16W - 0402")
      (fields
        (field (name "TOLERANCE") "1%")
        (field (name "PACKAGE") "0402")
        (field (name "Comment") "RC0402FR-0710KL")
        (field (name "CREATEDBY/DATE") "Nicolas V. (2018-11-20)")
        (field (name "VERIFIEDBY") "Nicolas V. (2018-11-20)")
      )
      (libsource (lib "GRAMS_MASTER_LIB") (part "RES_RC0402FR-0710KL"))
    )
    (comp (ref "R176")
      (value "10k")
      (footprint "RES_0402")
      (description "RES - 10K OHMS 1% 1/16W - 0402")
      (fields
        (field (name "TOLERANCE") "1%")
        (field (name "ASSEMBLY NOTE") "DNI")
        (field (name "PACKAGE") "0402")
        (field (name "Comment") "RC0402FR-0710KL")
        (field (name "CREATEDBY/DATE") "Nicolas V. (2018-11-20)")
        (field (name "VERIFIEDBY") "Nicolas V. (2018-11-20)")
      )
      (libsource (lib "GRAMS_MASTER_LIB") (part "RES_RC0402FR-0710KL"))
    )
    (comp (ref "R178")
      (value "0R")
      (footprint "RES_0402")
      (description "RES - 0R 1/16W 1A  - 0402")
      (fields
        (field (name "PACKAGE") "0402")
        (field (name "Comment") "RC0402FR-070RL")
        (field (name "CREATEDBY/DATE") "Keven Deslandes 2018-09-12")
        (field (name "VERIFIEDBY") "Caroline Paulin - 27 fév 2019")
      )
      (libsource (lib "GRAMS_MASTER_LIB") (part "RES_RC0402FR-070RL"))
    )
    (comp (ref "S3")
      (value "435171014816")
      (footprint "SWI_TACT_435171014816")
      (description "SWI - SWITCH TACTILE SPST-NO 0.05A 12V -SMD")
      (fields
        (field (name "CREATEDBY/DATE") "Hubert Dube - 22/07/20")
        (field (name "VERIFIEDBY") "Louis-Daniel Gaulin / 12-11-2020")
      )
      (libsource (lib "SWARMUS_LIB") (part "SWI_TACT_435171014816"))
    )
    (comp (ref "U1")
      (value "STM32H735ZGT6")
      (footprint "MCU_STM32H735ZGT6")
      (fields
        (field (name "CREATEDBY/DATE") "Philippe Arsenault/2021-04-08")
        (field (name "VERIFIEDBY") "Louis-Daniel Gaulin / 08-04-2021")
      )
      (libsource (lib "SWARMUS_LIB") (part "MCU_STM32H735ZGT6"))
    )
    (comp (ref "X4")
      (value "O 24,0-JO32-B-1V3-1-T1-LF")
      (footprint "OSC_O 24,0-JO32-B-1V3-1-T1-LF")
      (description "OSC - 24MHz XO (Standard) LVCMOS Oscillator 1.8V ~ 3.3V Enable/Disable 4-SMD, No Lead")
      (fields
        (field (name "TOLERANCE") "±50ppm")
        (field (name "CREATEDBY/DATE") "Louis-Daniel Gaulin / 13-04-2021")
        (field (name "VERIFIEDBY") "Philippe Arsenault/2021-04-14")
      )
      (libsource (lib "SWARMUS_LIB") (part "OSC_O 24,0-JO32-B-1V3-1-T1-LF"))
    )
  )
  (nets
    (net (code "1") (name "/CHAN_DET_0A") (class "Default")
      (node (ref "U1") (pin "120") (pinfunction "PD6_120") (pintype "passive"))
    )
    (net (code "2") (name "/CHAN_DET_0B") (class "Default")
      (node (ref "U1") (pin "94") (pinfunction "PC7_94") (pintype "passive"))
    )
    (net (code "3") (name "/CHAN_DET_0C") (class "Default")
      (node (ref "U1") (pin "60") (pinfunction "PE10_60") (pintype "passive"))
    )
    (net (code "4") (name "/CHAN_DET_1A") (class "Default")
      (node (ref "U1") (pin "117") (pinfunction "PD5_117") (pintype "passive"))
    )
    (net (code "5") (name "/CHAN_DET_1B") (class "Default")
      (node (ref "U1") (pin "93") (pinfunction "PC6_93") (pintype "passive"))
    )
    (net (code "6") (name "/CHAN_DET_1C") (class "Default")
      (node (ref "U1") (pin "59") (pinfunction "PE9_59") (pintype "passive"))
    )
    (net (code "7") (name "/CHAN_EN_0A") (class "Default")
      (node (ref "U1") (pin "125") (pinfunction "PG12_125") (pintype "passive"))
    )
    (net (code "8") (name "/CHAN_EN_0B") (class "Default")
      (node (ref "U1") (pin "97") (pinfunction "PA8_97") (pintype "passive"))
    )
    (net (code "9") (name "/CHAN_EN_0C") (class "Default")
      (node (ref "U1") (pin "61") (pinfunction "PE11_61") (pintype "passive"))
    )
    (net (code "10") (name "/CHAN_EN_1A") (class "Default")
      (node (ref "U1") (pin "114") (pinfunction "PD2_114") (pintype "passive"))
    )
    (net (code "11") (name "/CHAN_EN_1B") (class "Default")
      (node (ref "U1") (pin "84") (pinfunction "PD14_84") (pintype "passive"))
    )
    (net (code "12") (name "/CHAN_EN_1C") (class "Default")
      (node (ref "U1") (pin "52") (pinfunction "PF11_52") (pintype "passive"))
    )
    (net (code "13") (name "/CHAN_IRQ_0A") (class "Default")
      (node (ref "U1") (pin "123") (pinfunction "PG10_123") (pintype "passive"))
    )
    (net (code "14") (name "/CHAN_IRQ_0B") (class "Default")
      (node (ref "U1") (pin "95") (pinfunction "PC8_95") (pintype "passive"))
    )
    (net (code "15") (name "/CHAN_IRQ_0C") (class "Default")
      (node (ref "U1") (pin "65") (pinfunction "PE15_65") (pintype "passive"))
    )
    (net (code "16") (name "/CHAN_IRQ_1A") (class "Default")
      (node (ref "U1") (pin "115") (pinfunction "PD3_115") (pintype "passive"))
    )
    (net (code "17") (name "/CHAN_IRQ_1B") (class "Default")
      (node (ref "U1") (pin "82") (pinfunction "PD12_82") (pintype "passive"))
    )
    (net (code "18") (name "/CHAN_IRQ_1C") (class "Default")
      (node (ref "U1") (pin "45") (pinfunction "PA6_45") (pintype "passive"))
    )
    (net (code "19") (name "/CHAN_RESET_0A") (class "Default")
      (node (ref "U1") (pin "113") (pinfunction "PD1_113") (pintype "passive"))
    )
    (net (code "20") (name "/CHAN_RESET_0B") (class "Default")
      (node (ref "U1") (pin "83") (pinfunction "PD13_83") (pintype "passive"))
    )
    (net (code "21") (name "/CHAN_RESET_0C") (class "Default")
      (node (ref "U1") (pin "44") (pinfunction "PA5_44") (pintype "passive"))
    )
    (net (code "22") (name "/CHAN_RESET_1A") (class "Default")
      (node (ref "U1") (pin "112") (pinfunction "PD0_112") (pintype "passive"))
    )
    (net (code "23") (name "/CHAN_RESET_1B") (class "Default")
      (node (ref "U1") (pin "81") (pinfunction "PD11_81") (pintype "passive"))
    )
    (net (code "24") (name "/CHAN_RESET_1C") (class "Default")
      (node (ref "U1") (pin "43") (pinfunction "PA4_43") (pintype "passive"))
    )
    (net (code "25") (name "/CH_CL_PWR_EN") (class "Default")
      (node (ref "U1") (pin "86") (pinfunction "PG6_86") (pintype "passive"))
    )
    (net (code "26") (name "/CLK_OE_0#") (class "Default")
      (node (ref "U1") (pin "88") (pinfunction "PG8_88") (pintype "passive"))
    )
    (net (code "27") (name "/CLK_OE_1#") (class "Default")
      (node (ref "U1") (pin "87") (pinfunction "PG7_87") (pintype "passive"))
    )
    (net (code "28") (name "/DEBUG_EN#") (class "Default")
      (node (ref "U1") (pin "127") (pinfunction "PG14_127") (pintype "passive"))
    )
    (net (code "29") (name "/DEB_PWR_EN") (class "Default")
      (node (ref "U1") (pin "137") (pinfunction "PB9_137") (pintype "passive"))
    )
    (net (code "30") (name "/ETH_PWR_EN") (class "Default")
      (node (ref "U1") (pin "40") (pinfunction "PA3_40") (pintype "passive"))
    )
    (net (code "31") (name "/I2C_MISC_SCL") (class "Default")
      (node (ref "U1") (pin "133") (pinfunction "PB6_133") (pintype "passive"))
    )
    (net (code "32") (name "/I2C_MISC_SDA") (class "Default")
      (node (ref "U1") (pin "134") (pinfunction "PB7_134") (pintype "passive"))
    )
    (net (code "33") (name "/IMU_INT1") (class "Default")
      (node (ref "U1") (pin "9") (pinfunction "PC13_9") (pintype "passive"))
    )
    (net (code "34") (name "/IMU_INT2") (class "Default")
      (node (ref "U1") (pin "3") (pinfunction "PE4_3") (pintype "passive"))
    )
    (net (code "35") (name "/IO_EXP_INT#") (class "Default")
      (node (ref "U1") (pin "4") (pinfunction "PE5_4") (pintype "passive"))
    )
    (net (code "36") (name "/MCU_LED_0") (class "Default")
      (node (ref "D22") (pin "K") (pinfunction "K_K") (pintype "passive"))
      (node (ref "U1") (pin "30") (pinfunction "PC2_C_30") (pintype "passive"))
    )
    (net (code "37") (name "/MCU_LED_1") (class "Default")
      (node (ref "D23") (pin "K") (pinfunction "K_K") (pintype "passive"))
      (node (ref "U1") (pin "28") (pinfunction "PC0_28") (pintype "passive"))
    )
    (net (code "38") (name "/MCU_LED_2") (class "Default")
      (node (ref "D24") (pin "K") (pinfunction "K_K") (pintype "passive"))
      (node (ref "U1") (pin "24") (pinfunction "PF10_24") (pintype "passive"))
    )
    (net (code "39") (name "/MCU_LED_B") (class "Default")
      (node (ref "R1") (pin "2") (pinfunction "2_2") (pintype "passive"))
      (node (ref "U1") (pin "10") (pinfunction "PC14_-_OSC32_IN_10") (pintype "passive"))
    )
    (net (code "40") (name "/MCU_LED_G") (class "Default")
      (node (ref "R2") (pin "2") (pinfunction "2_2") (pintype "passive"))
      (node (ref "U1") (pin "11") (pinfunction "PC15_-_OSC32_OUT_11") (pintype "passive"))
    )
    (net (code "41") (name "/MCU_LED_HB") (class "Default")
      (node (ref "D25") (pin "K") (pinfunction "K_K") (pintype "passive"))
      (node (ref "U1") (pin "31") (pinfunction "PC3_C_31") (pintype "passive"))
    )
    (net (code "42") (name "/MCU_LED_R") (class "Default")
      (node (ref "R3") (pin "2") (pinfunction "2_2") (pintype "passive"))
      (node (ref "U1") (pin "20") (pinfunction "PF6_20") (pintype "passive"))
    )
    (net (code "43") (name "/MCU_OSC_EN") (class "Default")
      (node (ref "R64") (pin "2") (pinfunction "2_2") (pintype "passive"))
      (node (ref "X4") (pin "1") (pinfunction "EN_1") (pintype "passive"))
    )
    (net (code "44") (name "/MCU_RST#") (class "Default")
      (node (ref "R8") (pin "2") (pinfunction "2_2") (pintype "passive"))
      (node (ref "U1") (pin "27") (pinfunction "RST_27") (pintype "passive"))
    )
    (net (code "45") (name "/MEZ_ADC1_N") (class "Default")
      (node (ref "D30") (pin "2") (pinfunction "IO2_2") (pintype "passive"))
      (node (ref "D30") (pin "9") (pinfunction "NC_9") (pintype "passive"))
      (node (ref "J8") (pin "14") (pintype "passive"))
      (node (ref "U1") (pin "49") (pinfunction "PB0_49") (pintype "passive"))
    )
    (net (code "46") (name "/MEZ_ADC1_P") (class "Default")
      (node (ref "D30") (pin "1") (pinfunction "IO1_1") (pintype "passive"))
      (node (ref "D30") (pin "10") (pinfunction "NC_10") (pintype "passive"))
      (node (ref "J8") (pin "12") (pintype "passive"))
      (node (ref "U1") (pin "50") (pinfunction "PB1_50") (pintype "passive"))
    )
    (net (code "47") (name "/MEZ_I2C_SCL") (class "Default")
      (node (ref "D30") (pin "4") (pinfunction "IO3_4") (pintype "passive"))
      (node (ref "D30") (pin "7") (pinfunction "NC_7") (pintype "passive"))
      (node (ref "J8") (pin "13") (pintype "passive"))
      (node (ref "U1") (pin "53") (pinfunction "PF14_53") (pintype "passive"))
    )
    (net (code "48") (name "/MEZ_I2C_SDA") (class "Default")
      (node (ref "D30") (pin "5") (pinfunction "IO4_5") (pintype "passive"))
      (node (ref "D30") (pin "6") (pinfunction "NC_6") (pintype "passive"))
      (node (ref "J8") (pin "15") (pintype "passive"))
      (node (ref "U1") (pin "54") (pinfunction "PF15_54") (pintype "passive"))
    )
    (net (code "49") (name "/MEZ_SPI_MISO") (class "Default")
      (node (ref "D26") (pin "2") (pinfunction "IO2_2") (pintype "passive"))
      (node (ref "D26") (pin "9") (pinfunction "NC_9") (pintype "passive"))
      (node (ref "J8") (pin "7") (pintype "passive"))
      (node (ref "U1") (pin "63") (pinfunction "PE13_63") (pintype "passive"))
    )
    (net (code "50") (name "/MEZ_SPI_MOSI") (class "Default")
      (node (ref "D26") (pin "4") (pinfunction "IO3_4") (pintype "passive"))
      (node (ref "D26") (pin "7") (pinfunction "NC_7") (pintype "passive"))
      (node (ref "J8") (pin "9") (pintype "passive"))
      (node (ref "R173") (pin "2") (pinfunction "2_2") (pintype "passive"))
    )
    (net (code "51") (name "/MEZ_SPI_SCK") (class "Default")
      (node (ref "D26") (pin "1") (pinfunction "IO1_1") (pintype "passive"))
      (node (ref "D26") (pin "10") (pinfunction "NC_10") (pintype "passive"))
      (node (ref "J8") (pin "5") (pintype "passive"))
      (node (ref "R172") (pin "2") (pinfunction "2_2") (pintype "passive"))
    )
    (net (code "52") (name "/MEZ_UART_Rx") (class "Default")
      (node (ref "D29") (pin "1") (pinfunction "IO1_1") (pintype "passive"))
      (node (ref "D29") (pin "10") (pinfunction "NC_10") (pintype "passive"))
      (node (ref "J8") (pin "6") (pintype "passive"))
      (node (ref "U1") (pin "57") (pinfunction "PE7_57") (pintype "passive"))
    )
    (net (code "53") (name "/MEZ_UART_Tx") (class "Default")
      (node (ref "D29") (pin "2") (pinfunction "IO2_2") (pintype "passive"))
      (node (ref "D29") (pin "9") (pinfunction "NC_9") (pintype "passive"))
      (node (ref "J8") (pin "8") (pintype "passive"))
      (node (ref "U1") (pin "58") (pinfunction "PE8_58") (pintype "passive"))
    )
    (net (code "54") (name "/PHY_CRS") (class "Default")
      (node (ref "U1") (pin "46") (pinfunction "PA7_46") (pintype "passive"))
    )
    (net (code "55") (name "/PHY_MAC_CLK") (class "Default")
      (node (ref "U1") (pin "38") (pinfunction "PA1_38") (pintype "passive"))
    )
    (net (code "56") (name "/PHY_MDC") (class "Default")
      (node (ref "U1") (pin "29") (pinfunction "PC1_29") (pintype "passive"))
    )
    (net (code "57") (name "/PHY_MDIO") (class "Default")
      (node (ref "U1") (pin "39") (pinfunction "PA2_39") (pintype "passive"))
    )
    (net (code "58") (name "/PHY_RXD0") (class "Default")
      (node (ref "U1") (pin "47") (pinfunction "PC4_47") (pintype "passive"))
    )
    (net (code "59") (name "/PHY_RXD1") (class "Default")
      (node (ref "U1") (pin "48") (pinfunction "PC5_48") (pintype "passive"))
    )
    (net (code "60") (name "/PHY_TXD0") (class "Default")
      (node (ref "R165") (pin "1") (pinfunction "1_1") (pintype "passive"))
    )
    (net (code "61") (name "/PHY_TXD1") (class "Default")
      (node (ref "R167") (pin "1") (pinfunction "1_1") (pintype "passive"))
    )
    (net (code "62") (name "/PHY_TXEN") (class "Default")
      (node (ref "U1") (pin "67") (pinfunction "PB11_67") (pintype "passive"))
    )
    (net (code "63") (name "/PHY_nRST") (class "Default")
      (node (ref "U1") (pin "37") (pinfunction "PA0_37") (pintype "passive"))
    )
    (net (code "64") (name "/SPI_CLK_A") (class "Default")
      (node (ref "R171") (pin "2") (pinfunction "2_2") (pintype "passive"))
    )
    (net (code "65") (name "/SPI_CLK_B") (class "Default")
      (node (ref "R163") (pin "2") (pinfunction "2_2") (pintype "passive"))
    )
    (net (code "66") (name "/SPI_CLK_C") (class "Default")
      (node (ref "R162") (pin "1") (pinfunction "1_1") (pintype "passive"))
    )
    (net (code "67") (name "/SPI_MISO_A") (class "Default")
      (node (ref "U1") (pin "122") (pinfunction "PG9_122") (pintype "passive"))
    )
    (net (code "68") (name "/SPI_MISO_B") (class "Default")
      (node (ref "U1") (pin "110") (pinfunction "PC11_110") (pintype "passive"))
    )
    (net (code "69") (name "/SPI_MISO_C") (class "Default")
      (node (ref "U1") (pin "74") (pinfunction "PB14_74") (pintype "passive"))
    )
    (net (code "70") (name "/SPI_MOSI_A") (class "Default")
      (node (ref "R161") (pin "1") (pinfunction "1_1") (pintype "passive"))
    )
    (net (code "71") (name "/SPI_MOSI_B") (class "Default")
      (node (ref "R166") (pin "2") (pinfunction "2_2") (pintype "passive"))
    )
    (net (code "72") (name "/SPI_MOSI_C") (class "Default")
      (node (ref "R168") (pin "1") (pinfunction "1_1") (pintype "passive"))
    )
    (net (code "73") (name "/SPI_nCS_0A") (class "Default")
      (node (ref "U1") (pin "126") (pinfunction "PG13_126") (pintype "passive"))
    )
    (net (code "74") (name "/SPI_nCS_0B") (class "Default")
      (node (ref "U1") (pin "96") (pinfunction "PC9_96") (pintype "passive"))
    )
    (net (code "75") (name "/SPI_nCS_0C") (class "Default")
      (node (ref "U1") (pin "51") (pinfunction "PB2_51") (pintype "passive"))
    )
    (net (code "76") (name "/SPI_nCS_1A") (class "Default")
      (node (ref "U1") (pin "116") (pinfunction "PD4_116") (pintype "passive"))
    )
    (net (code "77") (name "/SPI_nCS_1B") (class "Default")
      (node (ref "U1") (pin "85") (pinfunction "PD15_85") (pintype "passive"))
    )
    (net (code "78") (name "/SPI_nCS_1C") (class "Default")
      (node (ref "U1") (pin "78") (pinfunction "PD10_78") (pintype "passive"))
    )
    (net (code "79") (name "/STM_JTCK") (class "Default")
      (node (ref "U1") (pin "107") (pinfunction "PA14_-_JTCK_107") (pintype "passive"))
    )
    (net (code "80") (name "/STM_JTDI") (class "Default")
      (node (ref "U1") (pin "108") (pinfunction "PA15_-_JTDI_108") (pintype "passive"))
    )
    (net (code "81") (name "/STM_JTDO") (class "Default")
      (node (ref "U1") (pin "130") (pinfunction "PB3_-_JTDC_130") (pintype "passive"))
    )
    (net (code "82") (name "/STM_JTMS") (class "Default")
      (node (ref "U1") (pin "102") (pinfunction "PA13_-_JTMS_102") (pintype "passive"))
    )
    (net (code "83") (name "/STM_NJTRST") (class "Default")
      (node (ref "U1") (pin "131") (pinfunction "PB4_-_JTRS_131") (pintype "passive"))
    )
    (net (code "84") (name "/STM_URx") (class "Default")
      (node (ref "U1") (pin "77") (pinfunction "PD9_77") (pintype "passive"))
    )
    (net (code "85") (name "/STM_UTx") (class "Default")
      (node (ref "U1") (pin "76") (pinfunction "PD8_76") (pintype "passive"))
    )
    (net (code "86") (name "/SYNC") (class "Default")
      (node (ref "U1") (pin "99") (pinfunction "PA10_99") (pintype "passive"))
    )
    (net (code "87") (name "/UART2_WROOM_Rx") (class "Default")
      (node (ref "U1") (pin "138") (pinfunction "PE0_138") (pintype "passive"))
    )
    (net (code "88") (name "/UART2_WROOM_Tx") (class "Default")
      (node (ref "U1") (pin "139") (pinfunction "PE1_139") (pintype "passive"))
    )
    (net (code "89") (name "/USB_PWR_DET#") (class "Default")
      (node (ref "U1") (pin "5") (pinfunction "PE6_5") (pintype "passive"))
    )
    (net (code "90") (name "/USB_STM_D_N") (class "Default")
      (node (ref "U1") (pin "100") (pinfunction "PA11_100") (pintype "passive"))
    )
    (net (code "91") (name "/USB_STM_D_P") (class "Default")
      (node (ref "U1") (pin "101") (pinfunction "PA12_101") (pintype "passive"))
    )
    (net (code "92") (name "/USB_STM_VBUS") (class "Default")
      (node (ref "U1") (pin "98") (pinfunction "PA9_98") (pintype "passive"))
    )
    (net (code "93") (name "/VCAP") (class "Default")
      (node (ref "C28") (pin "2") (pinfunction "2_2") (pintype "passive"))
      (node (ref "C29") (pin "2") (pinfunction "2_2") (pintype "passive"))
      (node (ref "C31") (pin "2") (pinfunction "2_2") (pintype "passive"))
      (node (ref "U1") (pin "103") (pinfunction "VCAP_103") (pintype "passive"))
      (node (ref "U1") (pin "140") (pinfunction "VCAP_140") (pintype "passive"))
      (node (ref "U1") (pin "68") (pinfunction "VCAP_68") (pintype "passive"))
    )
    (net (code "94") (name "/VDDA") (class "Default")
      (node (ref "C3") (pin "2") (pinfunction "2_2") (pintype "passive"))
      (node (ref "C6") (pin "1") (pinfunction "1_1") (pintype "passive"))
      (node (ref "L1") (pin "2") (pinfunction "2_2") (pintype "passive"))
      (node (ref "R130") (pin "1") (pinfunction "1_1") (pintype "passive"))
      (node (ref "U1") (pin "36") (pinfunction "VDDA_36") (pintype "passive"))
    )
    (net (code "95") (name "/VDDLDO") (class "Default")
      (node (ref "C20") (pin "2") (pinfunction "2_2") (pintype "passive"))
      (node (ref "C21") (pin "2") (pinfunction "2_2") (pintype "passive"))
      (node (ref "C22") (pin "2") (pinfunction "2_2") (pintype "passive"))
      (node (ref "C23") (pin "2") (pinfunction "2_2") (pintype "passive"))
      (node (ref "C24") (pin "2") (pinfunction "2_2") (pintype "passive"))
      (node (ref "C25") (pin "2") (pinfunction "2_2") (pintype "passive"))
      (node (ref "U1") (pin "105") (pinfunction "VDDLDO_105") (pintype "passive"))
      (node (ref "U1") (pin "143") (pinfunction "VDDLDO_143") (pintype "passive"))
      (node (ref "U1") (pin "70") (pinfunction "VDDLDO_70") (pintype "passive"))
    )
    (net (code "96") (name "/VSPI_CLK") (class "Default")
      (node (ref "R169") (pin "1") (pinfunction "1_1") (pintype "passive"))
    )
    (net (code "97") (name "/VSPI_MISO{slash}Q") (class "Default")
      (node (ref "U1") (pin "22") (pinfunction "PF8_22") (pintype "passive"))
    )
    (net (code "98") (name "/VSPI_MOSI{slash}D") (class "Default")
      (node (ref "R170") (pin "1") (pinfunction "1_1") (pintype "passive"))
    )
    (net (code "99") (name "/VSPI_nCS0") (class "Default")
      (node (ref "U1") (pin "136") (pinfunction "PB8_136") (pintype "passive"))
    )
    (net (code "100") (name "/WROOM_EN") (class "Default")
      (node (ref "U1") (pin "2") (pinfunction "PE3_2") (pintype "passive"))
    )
    (net (code "101") (name "/WROOM_GPIO0") (class "Default")
      (node (ref "U1") (pin "1") (pinfunction "PE2_1") (pintype "passive"))
    )
    (net (code "102") (name "/WR_PWR_EN") (class "Default")
      (node (ref "U1") (pin "132") (pinfunction "PB5_132") (pintype "passive"))
    )
    (net (code "103") (name "3V3") (class "Default")
      (node (ref "C1") (pin "2") (pinfunction "2_2") (pintype "passive"))
      (node (ref "C10") (pin "1") (pinfunction "1_1") (pintype "passive"))
      (node (ref "C11") (pin "2") (pinfunction "2_2") (pintype "passive"))
      (node (ref "C12") (pin "1") (pinfunction "1_1") (pintype "passive"))
      (node (ref "C123") (pin "2") (pinfunction "2_2") (pintype "passive"))
      (node (ref "C13") (pin "1") (pinfunction "1_1") (pintype "passive"))
      (node (ref "C14") (pin "1") (pinfunction "1_1") (pintype "passive"))
      (node (ref "C15") (pin "1") (pinfunction "1_1") (pintype "passive"))
      (node (ref "C16") (pin "1") (pinfunction "1_1") (pintype "passive"))
      (node (ref "C17") (pin "1") (pinfunction "1_1") (pintype "passive"))
      (node (ref "C18") (pin "1") (pinfunction "1_1") (pintype "passive"))
      (node (ref "C19") (pin "1") (pinfunction "1_1") (pintype "passive"))
      (node (ref "C2") (pin "1") (pinfunction "1_1") (pintype "passive"))
      (node (ref "C30") (pin "1") (pinfunction "1_1") (pintype "passive"))
      (node (ref "C5") (pin "2") (pinfunction "2_2") (pintype "passive"))
      (node (ref "C7") (pin "1") (pinfunction "1_1") (pintype "passive"))
      (node (ref "C8") (pin "1") (pinfunction "1_1") (pintype "passive"))
      (node (ref "C9") (pin "1") (pinfunction "1_1") (pintype "passive"))
      (node (ref "D1") (pin "3") (pinfunction "VDD_3") (pintype "passive"))
      (node (ref "D28") (pin "K") (pinfunction "K_K") (pintype "passive"))
      (node (ref "J8") (pin "1") (pintype "passive"))
      (node (ref "L1") (pin "1") (pinfunction "1_1") (pintype "passive"))
      (node (ref "R116") (pin "1") (pinfunction "1_1") (pintype "passive"))
      (node (ref "R129") (pin "1") (pinfunction "1_1") (pintype "passive"))
      (node (ref "R175") (pin "2") (pinfunction "2_2") (pintype "passive"))
      (node (ref "R23") (pin "1") (pinfunction "1_1") (pintype "passive"))
      (node (ref "R33") (pin "1") (pinfunction "1_1") (pintype "passive"))
      (node (ref "R5") (pin "1") (pinfunction "1_1") (pintype "passive"))
      (node (ref "R64") (pin "1") (pinfunction "1_1") (pintype "passive"))
      (node (ref "U1") (pin "106") (pinfunction "VDD_106") (pintype "passive"))
      (node (ref "U1") (pin "119") (pinfunction "VDD_119") (pintype "passive"))
      (node (ref "U1") (pin "129") (pinfunction "VDD_129") (pintype "passive"))
      (node (ref "U1") (pin "13") (pinfunction "VDD_13") (pintype "passive"))
      (node (ref "U1") (pin "144") (pinfunction "VDD_144") (pintype "passive"))
      (node (ref "U1") (pin "19") (pinfunction "VDD_19") (pintype "passive"))
      (node (ref "U1") (pin "32") (pinfunction "VDD_32") (pintype "passive"))
      (node (ref "U1") (pin "42") (pinfunction "VDD_42") (pintype "passive"))
      (node (ref "U1") (pin "56") (pinfunction "VDD_56") (pintype "passive"))
      (node (ref "U1") (pin "7") (pinfunction "VDD_7") (pintype "passive"))
      (node (ref "U1") (pin "71") (pinfunction "VDD_71") (pintype "passive"))
      (node (ref "U1") (pin "79") (pinfunction "VDD_79") (pintype "passive"))
      (node (ref "U1") (pin "8") (pinfunction "VBAT_8") (pintype "passive"))
      (node (ref "U1") (pin "90") (pinfunction "VDD50USB_90") (pintype "passive"))
      (node (ref "U1") (pin "92") (pinfunction "VDD_92") (pintype "passive"))
      (node (ref "X4") (pin "4") (pinfunction "VDC_4") (pintype "passive"))
    )
    (net (code "104") (name "5V") (class "Default")
      (node (ref "D27") (pin "1") (pinfunction "1_1") (pintype "passive"))
      (node (ref "J8") (pin "2") (pintype "passive"))
    )
    (net (code "105") (name "GND") (class "Default")
      (node (ref "C1") (pin "1") (pinfunction "1_1") (pintype "passive"))
      (node (ref "C10") (pin "2") (pinfunction "2_2") (pintype "passive"))
      (node (ref "C11") (pin "1") (pinfunction "1_1") (pintype "passive"))
      (node (ref "C12") (pin "2") (pinfunction "2_2") (pintype "passive"))
      (node (ref "C123") (pin "1") (pinfunction "1_1") (pintype "passive"))
      (node (ref "C13") (pin "2") (pinfunction "2_2") (pintype "passive"))
      (node (ref "C14") (pin "2") (pinfunction "2_2") (pintype "passive"))
      (node (ref "C15") (pin "2") (pinfunction "2_2") (pintype "passive"))
      (node (ref "C16") (pin "2") (pinfunction "2_2") (pintype "passive"))
      (node (ref "C17") (pin "2") (pinfunction "2_2") (pintype "passive"))
      (node (ref "C18") (pin "2") (pinfunction "2_2") (pintype "passive"))
      (node (ref "C19") (pin "2") (pinfunction "2_2") (pintype "passive"))
      (node (ref "C2") (pin "2") (pinfunction "2_2") (pintype "passive"))
      (node (ref "C20") (pin "1") (pinfunction "1_1") (pintype "passive"))
      (node (ref "C21") (pin "1") (pinfunction "1_1") (pintype "passive"))
      (node (ref "C22") (pin "1") (pinfunction "1_1") (pintype "passive"))
      (node (ref "C23") (pin "1") (pinfunction "1_1") (pintype "passive"))
      (node (ref "C24") (pin "1") (pinfunction "1_1") (pintype "passive"))
      (node (ref "C25") (pin "1") (pinfunction "1_1") (pintype "passive"))
      (node (ref "C28") (pin "1") (pinfunction "1_1") (pintype "passive"))
      (node (ref "C29") (pin "1") (pinfunction "1_1") (pintype "passive"))
      (node (ref "C3") (pin "1") (pinfunction "1_1") (pintype "passive"))
      (node (ref "C30") (pin "2") (pinfunction "2_2") (pintype "passive"))
      (node (ref "C31") (pin "1") (pinfunction "1_1") (pintype "passive"))
      (node (ref "C4") (pin "2") (pinfunction "2_2") (pintype "passive"))
      (node (ref "C5") (pin "1") (pinfunction "1_1") (pintype "passive"))
      (node (ref "C6") (pin "2") (pinfunction "2_2") (pintype "passive"))
      (node (ref "C7") (pin "2") (pinfunction "2_2") (pintype "passive"))
      (node (ref "C8") (pin "2") (pinfunction "2_2") (pintype "passive"))
      (node (ref "C9") (pin "2") (pinfunction "2_2") (pintype "passive"))
      (node (ref "D26") (pin "3") (pinfunction "VSS_3") (pintype "passive"))
      (node (ref "D26") (pin "8") (pinfunction "VSS_8") (pintype "passive"))
      (node (ref "D27") (pin "2") (pinfunction "2_2") (pintype "passive"))
      (node (ref "D28") (pin "A") (pinfunction "A_A") (pintype "passive"))
      (node (ref "D29") (pin "3") (pinfunction "VSS_3") (pintype "passive"))
      (node (ref "D29") (pin "8") (pinfunction "VSS_8") (pintype "passive"))
      (node (ref "D30") (pin "3") (pinfunction "VSS_3") (pintype "passive"))
      (node (ref "D30") (pin "8") (pinfunction "VSS_8") (pintype "passive"))
      (node (ref "HS1") (pin "1") (pinfunction "MH1_1") (pintype "passive"))
      (node (ref "HS1") (pin "2") (pinfunction "MH2_2") (pintype "passive"))
      (node (ref "J8") (pin "10") (pintype "passive"))
      (node (ref "J8") (pin "11") (pintype "passive"))
      (node (ref "J8") (pin "16") (pintype "passive"))
      (node (ref "J8") (pin "3") (pintype "passive"))
      (node (ref "J8") (pin "4") (pintype "passive"))
      (node (ref "MTH5") (pin "1") (pinfunction "1_1") (pintype "passive"))
      (node (ref "MTH6") (pin "1") (pinfunction "1_1") (pintype "passive"))
      (node (ref "R122") (pin "2") (pinfunction "2_2") (pintype "passive"))
      (node (ref "R176") (pin "2") (pinfunction "2_2") (pintype "passive"))
      (node (ref "R9") (pin "1") (pinfunction "1_1") (pintype "passive"))
      (node (ref "U1") (pin "104") (pinfunction "VSS_104") (pintype "passive"))
      (node (ref "U1") (pin "118") (pinfunction "VSS_118") (pintype "passive"))
      (node (ref "U1") (pin "12") (pinfunction "VSS_12") (pintype "passive"))
      (node (ref "U1") (pin "128") (pinfunction "VSS_128") (pintype "passive"))
      (node (ref "U1") (pin "14") (pinfunction "VSSSMPS_14") (pintype "passive"))
      (node (ref "U1") (pin "141") (pinfunction "VSS_141") (pintype "passive"))
      (node (ref "U1") (pin "16") (pinfunction "VDDSMPS_16") (pintype "passive"))
      (node (ref "U1") (pin "17") (pinfunction "VFBSMPS_17") (pintype "passive"))
      (node (ref "U1") (pin "18") (pinfunction "VSS_18") (pintype "passive"))
      (node (ref "U1") (pin "33") (pinfunction "VSS_33") (pintype "passive"))
      (node (ref "U1") (pin "34") (pinfunction "VSSA_34") (pintype "passive"))
      (node (ref "U1") (pin "41") (pinfunction "VSS_41") (pintype "passive"))
      (node (ref "U1") (pin "55") (pinfunction "VSS_55") (pintype "passive"))
      (node (ref "U1") (pin "6") (pinfunction "VSS_6") (pintype "passive"))
      (node (ref "U1") (pin "69") (pinfunction "VSS_69") (pintype "passive"))
      (node (ref "U1") (pin "80") (pinfunction "VSS_80") (pintype "passive"))
      (node (ref "U1") (pin "89") (pinfunction "VSS_89") (pintype "passive"))
      (node (ref "U1") (pin "91") (pinfunction "VDD33USB_91") (pintype "passive"))
      (node (ref "X4") (pin "2") (pinfunction "GND_2") (pintype "passive"))
    )
    (net (code "106") (name "Net-(C4-Pad1)") (class "Default")
      (node (ref "C4") (pin "1") (pinfunction "1_1") (pintype "passive"))
      (node (ref "R8") (pin "1") (pinfunction "1_1") (pintype "passive"))
      (node (ref "S3") (pin "3") (pinfunction "3_3") (pintype "passive"))
      (node (ref "S3") (pin "4") (pinfunction "4_4") (pintype "passive"))
    )
    (net (code "107") (name "Net-(D1-B)") (class "Default")
      (node (ref "D1") (pin "1") (pinfunction "B_1") (pintype "passive"))
      (node (ref "R1") (pin "1") (pinfunction "1_1") (pintype "passive"))
    )
    (net (code "108") (name "Net-(D1-G)") (class "Default")
      (node (ref "D1") (pin "2") (pinfunction "G_2") (pintype "passive"))
      (node (ref "R2") (pin "1") (pinfunction "1_1") (pintype "passive"))
    )
    (net (code "109") (name "Net-(D1-R)") (class "Default")
      (node (ref "D1") (pin "4") (pinfunction "R_4") (pintype "passive"))
      (node (ref "R3") (pin "1") (pinfunction "1_1") (pintype "passive"))
    )
    (net (code "110") (name "Net-(D22-PadA)") (class "Default")
      (node (ref "D22") (pin "A") (pinfunction "A_A") (pintype "passive"))
      (node (ref "R5") (pin "2") (pinfunction "2_2") (pintype "passive"))
    )
    (net (code "111") (name "Net-(D23-PadA)") (class "Default")
      (node (ref "D23") (pin "A") (pinfunction "A_A") (pintype "passive"))
      (node (ref "R23") (pin "2") (pinfunction "2_2") (pintype "passive"))
    )
    (net (code "112") (name "Net-(D24-PadA)") (class "Default")
      (node (ref "D24") (pin "A") (pinfunction "A_A") (pintype "passive"))
      (node (ref "R33") (pin "2") (pinfunction "2_2") (pintype "passive"))
    )
    (net (code "113") (name "Net-(D25-PadA)") (class "Default")
      (node (ref "D25") (pin "A") (pinfunction "A_A") (pintype "passive"))
      (node (ref "R129") (pin "2") (pinfunction "2_2") (pintype "passive"))
    )
    (net (code "114") (name "Net-(R9-Pad2)") (class "Default")
      (node (ref "R9") (pin "2") (pinfunction "2_2") (pintype "passive"))
      (node (ref "S3") (pin "1") (pinfunction "1_1") (pintype "passive"))
      (node (ref "S3") (pin "2") (pinfunction "2_2") (pintype "passive"))
    )
    (net (code "115") (name "Net-(U1A-BOOT0)") (class "Default")
      (node (ref "R116") (pin "2") (pinfunction "2_2") (pintype "passive"))
      (node (ref "R122") (pin "1") (pinfunction "1_1") (pintype "passive"))
      (node (ref "U1") (pin "135") (pinfunction "BOOT0_135") (pintype "passive"))
    )
    (net (code "116") (name "Net-(U1A-PDR_ON)") (class "Default")
      (node (ref "R175") (pin "1") (pinfunction "1_1") (pintype "passive"))
      (node (ref "R176") (pin "1") (pinfunction "1_1") (pintype "passive"))
      (node (ref "U1") (pin "142") (pinfunction "PDR_ON_142") (pintype "passive"))
    )
    (net (code "117") (name "Net-(U1A-VREF+)") (class "Default")
      (node (ref "R130") (pin "2") (pinfunction "2_2") (pintype "passive"))
      (node (ref "U1") (pin "35") (pinfunction "VREF+_35") (pintype "passive"))
    )
    (net (code "118") (name "Net-(U1B-PB10)") (class "Default")
      (node (ref "R162") (pin "2") (pinfunction "2_2") (pintype "passive"))
      (node (ref "U1") (pin "66") (pinfunction "PB10_66") (pintype "passive"))
    )
    (net (code "119") (name "Net-(U1B-PB12)") (class "Default")
      (node (ref "R165") (pin "2") (pinfunction "2_2") (pintype "passive"))
      (node (ref "U1") (pin "72") (pinfunction "PB12_72") (pintype "passive"))
    )
    (net (code "120") (name "Net-(U1B-PB13)") (class "Default")
      (node (ref "R167") (pin "2") (pinfunction "2_2") (pintype "passive"))
      (node (ref "U1") (pin "73") (pinfunction "PB13_73") (pintype "passive"))
    )
    (net (code "121") (name "Net-(U1B-PB15)") (class "Default")
      (node (ref "R168") (pin "2") (pinfunction "2_2") (pintype "passive"))
      (node (ref "U1") (pin "75") (pinfunction "PB15_75") (pintype "passive"))
    )
    (net (code "122") (name "Net-(U1C-PC10)") (class "Default")
      (node (ref "R163") (pin "1") (pinfunction "1_1") (pintype "passive"))
      (node (ref "U1") (pin "109") (pinfunction "PC10_109") (pintype "passive"))
    )
    (net (code "123") (name "Net-(U1C-PC12)") (class "Default")
      (node (ref "R166") (pin "1") (pinfunction "1_1") (pintype "passive"))
      (node (ref "U1") (pin "111") (pinfunction "PC12_111") (pintype "passive"))
    )
    (net (code "124") (name "Net-(U1C-PD7)") (class "Default")
      (node (ref "R161") (pin "2") (pinfunction "2_2") (pintype "passive"))
      (node (ref "U1") (pin "121") (pinfunction "PD7_121") (pintype "passive"))
    )
    (net (code "125") (name "Net-(U1D-PE12)") (class "Default")
      (node (ref "R172") (pin "1") (pinfunction "1_1") (pintype "passive"))
      (node (ref "U1") (pin "62") (pinfunction "PE12_62") (pintype "passive"))
    )
    (net (code "126") (name "Net-(U1D-PE14)") (class "Default")
      (node (ref "R173") (pin "1") (pinfunction "1_1") (pintype "passive"))
      (node (ref "U1") (pin "64") (pinfunction "PE14_64") (pintype "passive"))
    )
    (net (code "127") (name "Net-(U1D-PF7)") (class "Default")
      (node (ref "R169") (pin "2") (pinfunction "2_2") (pintype "passive"))
      (node (ref "U1") (pin "21") (pinfunction "PF7_21") (pintype "passive"))
    )
    (net (code "128") (name "Net-(U1D-PF9)") (class "Default")
      (node (ref "R170") (pin "2") (pinfunction "2_2") (pintype "passive"))
      (node (ref "U1") (pin "23") (pinfunction "PF9_23") (pintype "passive"))
    )
    (net (code "129") (name "Net-(U1E-PG11)") (class "Default")
      (node (ref "R171") (pin "1") (pinfunction "1_1") (pintype "passive"))
      (node (ref "U1") (pin "124") (pinfunction "PG11_124") (pintype "passive"))
    )
    (net (code "130") (name "Net-(U1E-PH0-OSC_IN)") (class "Default")
      (node (ref "R178") (pin "2") (pinfunction "2_2") (pintype "passive"))
      (node (ref "U1") (pin "25") (pinfunction "PH0-OSC_IN_25") (pintype "passive"))
    )
    (net (code "131") (name "Net-(X4-OUTPUT)") (class "Default")
      (node (ref "R178") (pin "1") (pinfunction "1_1") (pintype "passive"))
      (node (ref "X4") (pin "3") (pinfunction "OUTPUT_3") (pintype "passive"))
    )
    (net (code "132") (name "unconnected-(D26-IO4-Pad5)") (class "Default")
      (node (ref "D26") (pin "5") (pinfunction "IO4_5") (pintype "passive+no_connect"))
    )
    (net (code "133") (name "unconnected-(D26-NC-Pad6)") (class "Default")
      (node (ref "D26") (pin "6") (pinfunction "NC_6") (pintype "passive+no_connect"))
    )
    (net (code "134") (name "unconnected-(D29-IO3-Pad4)") (class "Default")
      (node (ref "D29") (pin "4") (pinfunction "IO3_4") (pintype "passive+no_connect"))
    )
    (net (code "135") (name "unconnected-(D29-IO4-Pad5)") (class "Default")
      (node (ref "D29") (pin "5") (pinfunction "IO4_5") (pintype "passive+no_connect"))
    )
    (net (code "136") (name "unconnected-(D29-NC-Pad6)") (class "Default")
      (node (ref "D29") (pin "6") (pinfunction "NC_6") (pintype "passive+no_connect"))
    )
    (net (code "137") (name "unconnected-(D29-NC-Pad7)") (class "Default")
      (node (ref "D29") (pin "7") (pinfunction "NC_7") (pintype "passive+no_connect"))
    )
    (net (code "138") (name "unconnected-(U1A-VLXSMPS-Pad15)") (class "Default")
      (node (ref "U1") (pin "15") (pinfunction "VLXSMPS_15") (pintype "passive+no_connect"))
    )
    (net (code "139") (name "unconnected-(U1E-PH0-OSC_OUT-Pad26)") (class "Default")
      (node (ref "U1") (pin "26") (pinfunction "PH0-OSC_OUT_26") (pintype "passive+no_connect"))
    )
  )
)
